# TFTLCD.net
KiCad netlist of a schematic drawn in Altium Designer
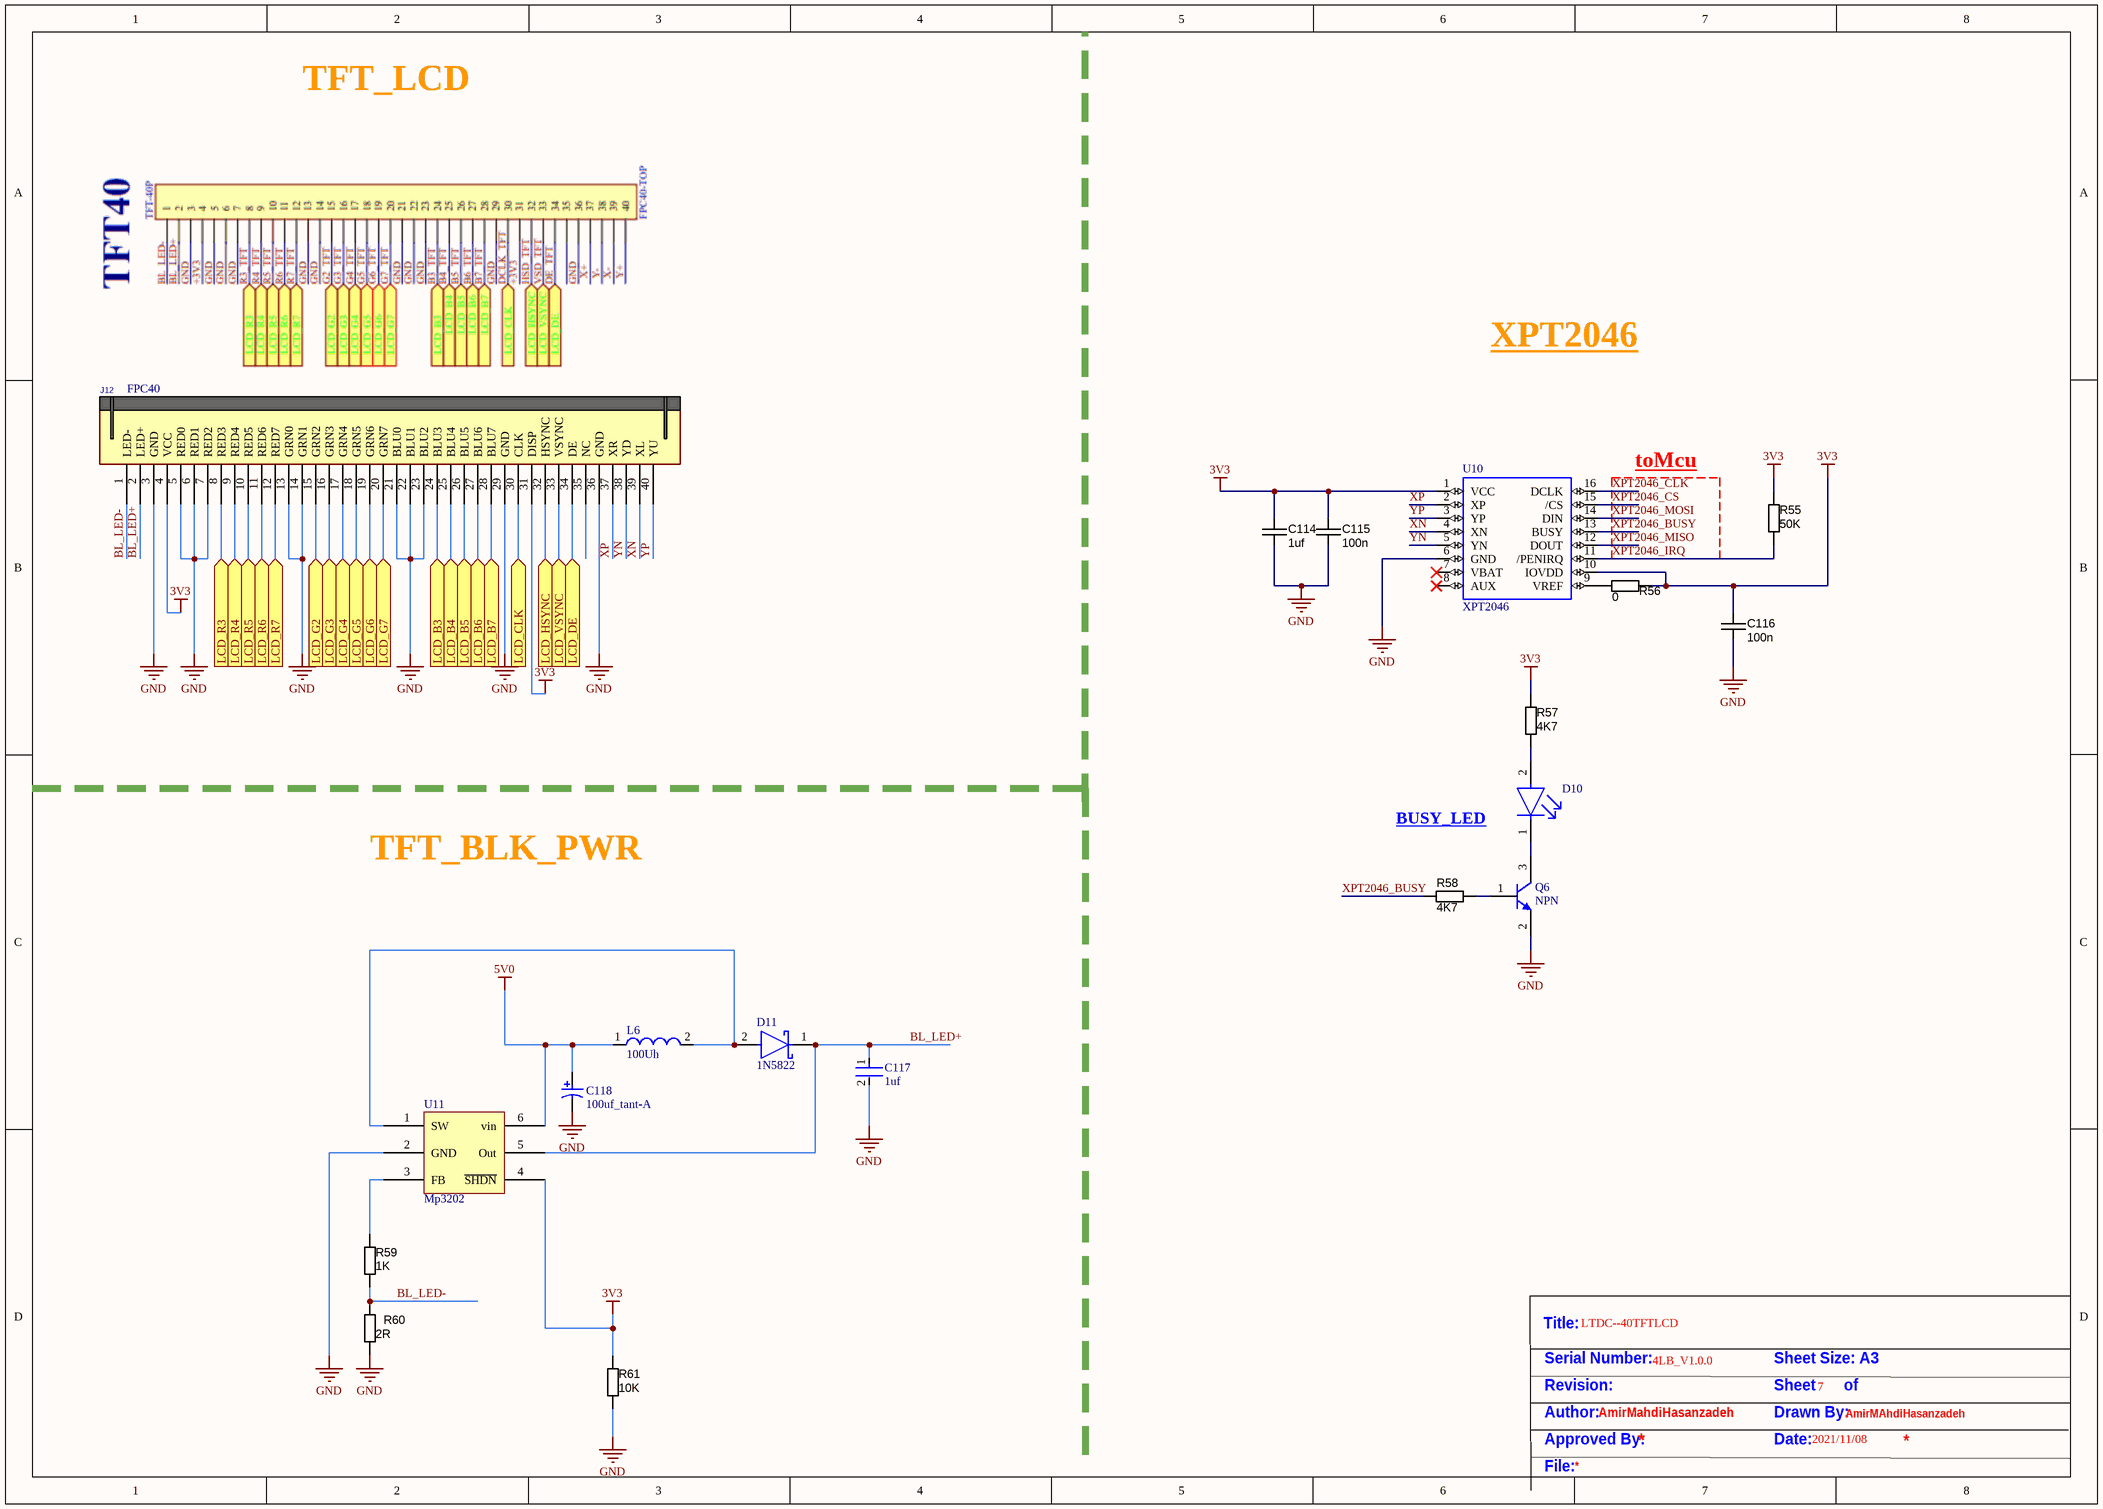
[diagram p0: TFTLCD.SchDoc]

(export (version "E")
  (design (tool "Eeschema 10.0.6"))
  (components
    (comp (ref "C114")
      (value "1uf")
      (footprint "CAPC3216X180N")
      (description "Capacitor SMD Cer 47nF 10% 50V X7R 1206")
      (fields (field (name "TOLERANCE") "±10%"))
      (libsource (lib "PBL - Capacitors") (part "CAPC_47n_1206_X7R_50V_10%"))
    )
    (comp (ref "C115")
      (value "100n")
      (footprint "CAPC1608X90N")
      (description "Capacitor SMD Cer 100nF 10% 50V X7R 0603")
      (fields (field (name "TOLERANCE") "±10%") (field (name "Comment") "approved sub OK"))
      (libsource (lib "PBL - Capacitors") (part "CAPC_100n_0603_X7R_50V_10%"))
    )
    (comp (ref "C116")
      (value "100n")
      (footprint "CAPC1608X90N")
      (description "Capacitor SMD Cer 100nF 10% 50V X7R 0603")
      (fields (field (name "TOLERANCE") "±10%") (field (name "Comment") "approved sub OK"))
      (libsource (lib "PBL - Capacitors") (part "CAPC_100n_0603_X7R_50V_10%"))
    )
    (comp (ref "C117")
      (value "1uf")
      (footprint "FP-GRM31C-0_2-e0_3_0_8-MFG")
      (description "Chip Multilayer Ceramic Capacitors for General Purpose, 1206, 22uF, X7R, 15%, 10%, 10V")
      (fields (field (name "VOLTAGE") "10V") (field (name "TOLERANCE") "10%"))
      (libsource (lib "Altium Content Vault") (part "02cd4be3c70576c341d710602a673aa"))
    )
    (comp (ref "C118")
      (value "100uf_tant-A")
      (footprint "AVX-TPSA106K010R1800_M")
      (description "Tantalum Capacitor, 22uF, +/- 10%, 10 V, -55 to 125 degC, 2-Pin Molded, RoHS, Tape and Reel")
      (fields (field (name "MANUFACTURER") "AVX") (field (name "TOLERANCE") "±10%"))
      (libsource (lib "Altium Content Vault") (part "CAP-P-2"))
    )
    (comp (ref "D10")
      (value "LTST-C191TBKT")
      (footprint "FP-LTST-C191TBKT-MFG")
      (description "LED BLUE CLEAR CHIP SMD")
      (libsource (lib "Altium Content Vault") (part "8706943c75ba83719d021d2fdc84c58"))
    )
    (comp (ref "D11")
      (value "1N5822")
      (footprint "FP-DO-201AD-MFG")
      (description "DIODE SCHOTTKY 40V 3A DO201AD")
      (fields
        (field (name "OCTOPART") "https://octopart.com/1n5822-stmicroelectronics-323225")
        (field (name "MANUFACTURER") "STMicroelectronics")
      )
      (libsource (lib "Altium Content Vault") (part "1d6ec82d83fb6aee721767c19dac4b9"))
    )
    (comp (ref "J12")
      (value "FPC40")
      (footprint "FPC50_40")
      (description "CONN, FPC, 0.50mm pitch, RightAngle, Bot. Contact")
      (fields (field (name "MANF") "MOLEX, Hirose") (field (name "MANF_P#") "54132‐4062, FH12-40S-0.5SH"))
      (libsource (lib "conn_fpc") (part "FPC50_40"))
    )
    (comp (ref "L6")
      (value "100Uh")
      (footprint "WE-PD2-M")
      (description "SMD Power Inductor WE-PD2, L = 100 µH")
      (libsource (lib "Altium Content Vault") (part "PAS-IND-INDUCTOR-2"))
    )
    (comp (ref "Q6")
      (value "NPN")
      (footprint "SOT23-3")
      (description "NPN Bipolar Transistor")
      (fields (field (name "PUBLISHER") "Altium Limited"))
      (libsource (lib "Miscellaneous Devices") (part "NPN"))
    )
    (comp (ref "R55")
      (value "50K")
      (footprint "RESC1608X55N")
      (description "Resistor SMD chip 10K Ohm 0.1W 5% 0603")
      (fields (field (name "TOLERANCE") "±5%") (field (name "Comment") "Thick Film"))
      (libsource (lib "PBL - Resistors") (part "RES_4K7_0603_5%"))
    )
    (comp (ref "R56")
      (value "0")
      (footprint "RESC1608X55N")
      (description "Resistor SMD chip 0 Ohm 0.1W 5% 0603")
      (fields (field (name "TOLERANCE") "±5%") (field (name "Comment") "Thick Film"))
      (libsource (lib "") (part "RES_4K7_0603_5%_2"))
    )
    (comp (ref "R57")
      (value "4K7")
      (footprint "RESC1608X55N")
      (description "Resistor SMD chip 4.7k Ohm 0.1W 5% 0603")
      (fields (field (name "TOLERANCE") "±5%") (field (name "Comment") "Thick Film"))
      (libsource (lib "") (part "RES_4K7_0603_5%_1"))
    )
    (comp (ref "R58")
      (value "4K7")
      (footprint "RESC1608X55N")
      (description "Resistor SMD chip 4.7k Ohm 0.1W 5% 0603")
      (fields (field (name "TOLERANCE") "±5%") (field (name "Comment") "Thick Film"))
      (libsource (lib "") (part "RES_4K7_0603_5%_3"))
    )
    (comp (ref "R59")
      (value "1K")
      (footprint "RESC1608X55N")
      (description "Resistor SMD chip 4.7k Ohm 0.1W 5% 0603")
      (fields (field (name "TOLERANCE") "±5%") (field (name "Comment") "Thick Film"))
      (libsource (lib "PBL - Resistors") (part "RES_4K7_0603_5%"))
    )
    (comp (ref "R60")
      (value "2R")
      (footprint "RESC1608X55N")
      (description "Resistor SMD chip 4.7k Ohm 0.1W 5% 0603")
      (fields (field (name "TOLERANCE") "±5%") (field (name "Comment") "Thick Film"))
      (libsource (lib "") (part "RES_4K7_0603_5%_1"))
    )
    (comp (ref "R61")
      (value "10K")
      (footprint "RESC1608X55N")
      (description "Resistor SMD chip 4.7k Ohm 0.1W 5% 0603")
      (fields (field (name "TOLERANCE") "±5%") (field (name "Comment") "Thick Film"))
      (libsource (lib "") (part "RES_4K7_0603_5%_1"))
    )
    (comp (ref "U10")
      (value "XPT2046")
      (footprint "TSSOP-16")
      (description "RASPBERRY PI 3.5 TFT DISPLAY")
      (fields (field (name "MF") "Xptek"))
      (libsource (lib "XPT2046") (part "XPT2046"))
    )
    (comp (ref "U11")
      (value "Mp3202")
      (footprint "SOT95P280X145-6N")
      (libsource (lib "Mp3202") (part "Mp3202"))
    )
  )
  (nets
    (net (code "1") (name "/BL_LED+") (class "Default")
      (node (ref "C117") (pin "1") (pinfunction "1_1") (pintype "passive"))
      (node (ref "D11") (pin "1") (pinfunction "C_1") (pintype "passive"))
      (node (ref "J12") (pin "2") (pinfunction "LED+_2") (pintype "passive"))
      (node (ref "U11") (pin "5") (pinfunction "Out_5") (pintype "passive"))
    )
    (net (code "2") (name "/BL_LED-") (class "Default")
      (node (ref "J12") (pin "1") (pinfunction "LED-_1") (pintype "passive"))
      (node (ref "R59") (pin "2") (pinfunction "2_2") (pintype "passive"))
      (node (ref "R60") (pin "2") (pinfunction "2_2") (pintype "passive"))
    )
    (net (code "3") (name "/LCD_B3") (class "Default")
      (node (ref "J12") (pin "24") (pinfunction "BLU3_24") (pintype "passive"))
    )
    (net (code "4") (name "/LCD_B4") (class "Default")
      (node (ref "J12") (pin "25") (pinfunction "BLU4_25") (pintype "passive"))
    )
    (net (code "5") (name "/LCD_B5") (class "Default")
      (node (ref "J12") (pin "26") (pinfunction "BLU5_26") (pintype "passive"))
    )
    (net (code "6") (name "/LCD_B6") (class "Default")
      (node (ref "J12") (pin "27") (pinfunction "BLU6_27") (pintype "passive"))
    )
    (net (code "7") (name "/LCD_B7") (class "Default")
      (node (ref "J12") (pin "28") (pinfunction "BLU7_28") (pintype "passive"))
    )
    (net (code "8") (name "/LCD_CLK") (class "Default")
      (node (ref "J12") (pin "30") (pinfunction "CLK_30") (pintype "passive"))
    )
    (net (code "9") (name "/LCD_DE") (class "Default")
      (node (ref "J12") (pin "34") (pinfunction "DE_34") (pintype "passive"))
    )
    (net (code "10") (name "/LCD_G2") (class "Default")
      (node (ref "J12") (pin "15") (pinfunction "GRN2_15") (pintype "passive"))
    )
    (net (code "11") (name "/LCD_G3") (class "Default")
      (node (ref "J12") (pin "16") (pinfunction "GRN3_16") (pintype "passive"))
    )
    (net (code "12") (name "/LCD_G4") (class "Default")
      (node (ref "J12") (pin "17") (pinfunction "GRN4_17") (pintype "passive"))
    )
    (net (code "13") (name "/LCD_G5") (class "Default")
      (node (ref "J12") (pin "18") (pinfunction "GRN5_18") (pintype "passive"))
    )
    (net (code "14") (name "/LCD_G6") (class "Default")
      (node (ref "J12") (pin "19") (pinfunction "GRN6_19") (pintype "passive"))
    )
    (net (code "15") (name "/LCD_G7") (class "Default")
      (node (ref "J12") (pin "20") (pinfunction "GRN7_20") (pintype "passive"))
    )
    (net (code "16") (name "/LCD_HSYNC") (class "Default")
      (node (ref "J12") (pin "32") (pinfunction "HSYNC_32") (pintype "passive"))
    )
    (net (code "17") (name "/LCD_R3") (class "Default")
      (node (ref "J12") (pin "8") (pinfunction "RED3_8") (pintype "passive"))
    )
    (net (code "18") (name "/LCD_R4") (class "Default")
      (node (ref "J12") (pin "9") (pinfunction "RED4_9") (pintype "passive"))
    )
    (net (code "19") (name "/LCD_R5") (class "Default")
      (node (ref "J12") (pin "10") (pinfunction "RED5_10") (pintype "passive"))
    )
    (net (code "20") (name "/LCD_R6") (class "Default")
      (node (ref "J12") (pin "11") (pinfunction "RED6_11") (pintype "passive"))
    )
    (net (code "21") (name "/LCD_R7") (class "Default")
      (node (ref "J12") (pin "12") (pinfunction "RED7_12") (pintype "passive"))
    )
    (net (code "22") (name "/LCD_VSYNC") (class "Default")
      (node (ref "J12") (pin "33") (pinfunction "VSYNC_33") (pintype "passive"))
    )
    (net (code "23") (name "/XN") (class "Default")
      (node (ref "J12") (pin "39") (pinfunction "XL_39") (pintype "passive"))
      (node (ref "U10") (pin "4") (pinfunction "XN_4") (pintype "bidirectional"))
    )
    (net (code "24") (name "/XP") (class "Default")
      (node (ref "J12") (pin "37") (pinfunction "XR_37") (pintype "passive"))
      (node (ref "U10") (pin "2") (pinfunction "XP_2") (pintype "bidirectional"))
    )
    (net (code "25") (name "/XPT2046_BUSY") (class "Default")
      (node (ref "R58") (pin "1") (pinfunction "1_1") (pintype "passive"))
      (node (ref "U10") (pin "13") (pinfunction "BUSY_13") (pintype "bidirectional"))
    )
    (net (code "26") (name "/XPT2046_CLK") (class "Default")
      (node (ref "U10") (pin "16") (pinfunction "DCLK_16") (pintype "bidirectional"))
    )
    (net (code "27") (name "/XPT2046_CS") (class "Default")
      (node (ref "U10") (pin "15") (pinfunction "/CS_15") (pintype "bidirectional"))
    )
    (net (code "28") (name "/XPT2046_IRQ") (class "Default")
      (node (ref "R55") (pin "2") (pinfunction "2_2") (pintype "passive"))
      (node (ref "U10") (pin "11") (pinfunction "/PENIRQ_11") (pintype "bidirectional"))
    )
    (net (code "29") (name "/XPT2046_MISO") (class "Default")
      (node (ref "U10") (pin "12") (pinfunction "DOUT_12") (pintype "bidirectional"))
    )
    (net (code "30") (name "/XPT2046_MOSI") (class "Default")
      (node (ref "U10") (pin "14") (pinfunction "DIN_14") (pintype "bidirectional"))
    )
    (net (code "31") (name "/YN") (class "Default")
      (node (ref "J12") (pin "38") (pinfunction "YD_38") (pintype "passive"))
      (node (ref "U10") (pin "5") (pinfunction "YN_5") (pintype "bidirectional"))
    )
    (net (code "32") (name "/YP") (class "Default")
      (node (ref "J12") (pin "40") (pinfunction "YU_40") (pintype "passive"))
      (node (ref "U10") (pin "3") (pinfunction "YP_3") (pintype "bidirectional"))
    )
    (net (code "33") (name "3V3") (class "Default")
      (node (ref "C114") (pin "1") (pintype "passive"))
      (node (ref "C115") (pin "1") (pintype "passive"))
      (node (ref "C116") (pin "1") (pintype "passive"))
      (node (ref "J12") (pin "31") (pinfunction "DISP_31") (pintype "passive"))
      (node (ref "J12") (pin "4") (pinfunction "VCC_4") (pintype "passive"))
      (node (ref "R55") (pin "1") (pinfunction "1_1") (pintype "passive"))
      (node (ref "R56") (pin "1") (pinfunction "1_1") (pintype "passive"))
      (node (ref "R57") (pin "2") (pinfunction "2_2") (pintype "passive"))
      (node (ref "R61") (pin "2") (pinfunction "2_2") (pintype "passive"))
      (node (ref "U10") (pin "1") (pinfunction "VCC_1") (pintype "bidirectional"))
      (node (ref "U10") (pin "10") (pinfunction "IOVDD_10") (pintype "bidirectional"))
      (node (ref "U11") (pin "4") (pinfunction "~{SHDN}_4") (pintype "passive"))
    )
    (net (code "34") (name "5V0") (class "Default")
      (node (ref "C118") (pin "1") (pinfunction "1_1") (pintype "passive"))
      (node (ref "L6") (pin "1") (pinfunction "1_1") (pintype "passive"))
      (node (ref "U11") (pin "6") (pinfunction "vin_6") (pintype "passive"))
    )
    (net (code "35") (name "GND") (class "Default")
      (node (ref "C114") (pin "2") (pintype "passive"))
      (node (ref "C115") (pin "2") (pintype "passive"))
      (node (ref "C116") (pin "2") (pintype "passive"))
      (node (ref "C117") (pin "2") (pinfunction "2_2") (pintype "passive"))
      (node (ref "C118") (pin "2") (pinfunction "2_2") (pintype "passive"))
      (node (ref "J12") (pin "13") (pinfunction "GRN0_13") (pintype "passive"))
      (node (ref "J12") (pin "14") (pinfunction "GRN1_14") (pintype "passive"))
      (node (ref "J12") (pin "21") (pinfunction "BLU0_21") (pintype "passive"))
      (node (ref "J12") (pin "22") (pinfunction "BLU1_22") (pintype "passive"))
      (node (ref "J12") (pin "23") (pinfunction "BLU2_23") (pintype "passive"))
      (node (ref "J12") (pin "29") (pinfunction "GND_29") (pintype "passive"))
      (node (ref "J12") (pin "3") (pinfunction "GND_3") (pintype "passive"))
      (node (ref "J12") (pin "36") (pinfunction "GND_36") (pintype "passive"))
      (node (ref "J12") (pin "5") (pinfunction "RED0_5") (pintype "passive"))
      (node (ref "J12") (pin "6") (pinfunction "RED1_6") (pintype "passive"))
      (node (ref "J12") (pin "7") (pinfunction "RED2_7") (pintype "passive"))
      (node (ref "Q6") (pin "2") (pinfunction "E_2") (pintype "passive"))
      (node (ref "R60") (pin "1") (pinfunction "1_1") (pintype "passive"))
      (node (ref "R61") (pin "1") (pinfunction "1_1") (pintype "passive"))
      (node (ref "U10") (pin "6") (pinfunction "GND_6") (pintype "bidirectional"))
      (node (ref "U11") (pin "2") (pinfunction "GND_2") (pintype "passive"))
    )
    (net (code "36") (name "Net-(D10-A)") (class "Default")
      (node (ref "D10") (pin "2") (pinfunction "A_2") (pintype "passive"))
      (node (ref "R57") (pin "1") (pinfunction "1_1") (pintype "passive"))
    )
    (net (code "37") (name "Net-(D10-C)") (class "Default")
      (node (ref "D10") (pin "1") (pinfunction "C_1") (pintype "passive"))
      (node (ref "Q6") (pin "3") (pinfunction "C_3") (pintype "passive"))
    )
    (net (code "38") (name "Net-(D11-A)") (class "Default")
      (node (ref "D11") (pin "2") (pinfunction "A_2") (pintype "passive"))
      (node (ref "L6") (pin "2") (pinfunction "2_2") (pintype "passive"))
      (node (ref "U11") (pin "1") (pinfunction "SW_1") (pintype "passive"))
    )
    (net (code "39") (name "Net-(Q6-B)") (class "Default")
      (node (ref "Q6") (pin "1") (pinfunction "B_1") (pintype "passive"))
      (node (ref "R58") (pin "2") (pinfunction "2_2") (pintype "passive"))
    )
    (net (code "40") (name "Net-(U10-VREF)") (class "Default")
      (node (ref "R56") (pin "2") (pinfunction "2_2") (pintype "passive"))
      (node (ref "U10") (pin "9") (pinfunction "VREF_9") (pintype "bidirectional"))
    )
    (net (code "41") (name "Net-(U11-FB)") (class "Default")
      (node (ref "R59") (pin "1") (pinfunction "1_1") (pintype "passive"))
      (node (ref "U11") (pin "3") (pinfunction "FB_3") (pintype "passive"))
    )
    (net (code "42") (name "unconnected-(J12-NC-Pad35)") (class "Default")
      (node (ref "J12") (pin "35") (pinfunction "NC_35") (pintype "passive"))
    )
    (net (code "43") (name "unconnected-(U10-AUX-Pad8)") (class "Default")
      (node (ref "U10") (pin "8") (pinfunction "AUX_8") (pintype "bidirectional+no_connect"))
    )
    (net (code "44") (name "unconnected-(U10-VBAT-Pad7)") (class "Default")
      (node (ref "U10") (pin "7") (pinfunction "VBAT_7") (pintype "bidirectional+no_connect"))
    )
  )
)
